# sustentationAvecPC.net
KiCad netlist of a schematic drawn in Altium Designer
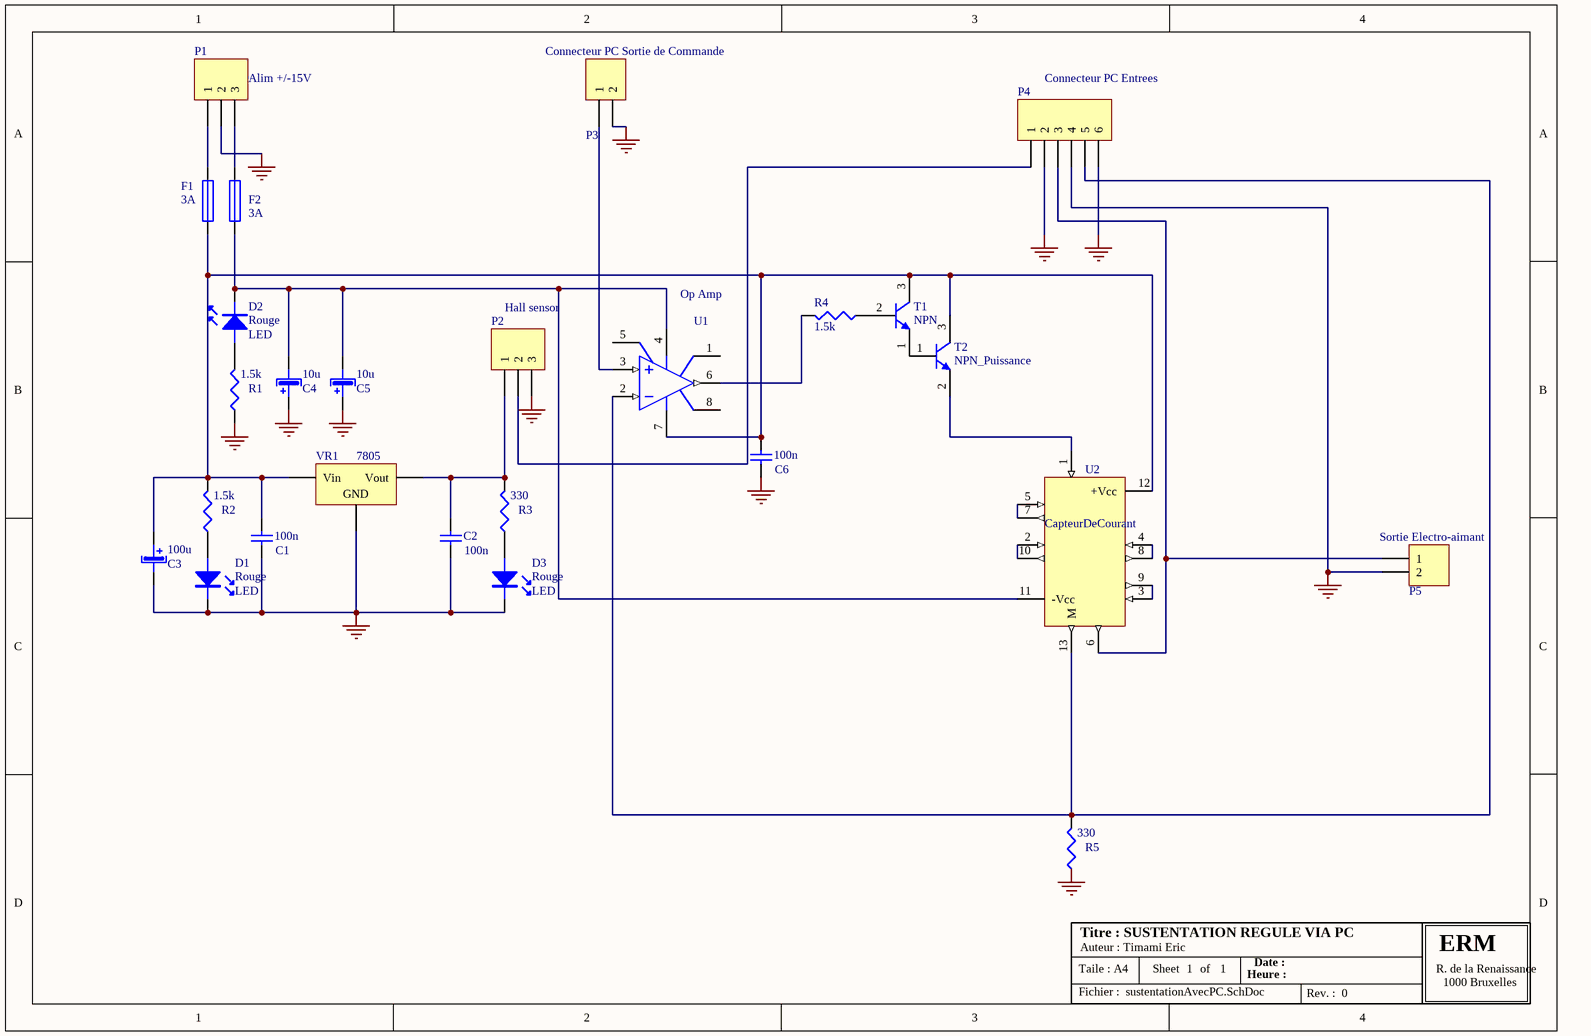
[diagram p0: sustentationAvecPC.SchDoc]

(export (version "E")
  (design (tool "Eeschema 10.0.6"))
  (components
    (comp (ref "C1")
      (value "100n")
      (footprint "Capa_100n")
      (description "Condensateur")
      (fields (field (name "DESIGNER") "ECAM 2004"))
      (libsource (lib "AntiNuisibles") (part "Condensateur"))
    )
    (comp (ref "C2")
      (value "100n")
      (footprint "Capa_100n")
      (description "Condensateur")
      (fields (field (name "DESIGNER") "ECAM 2004"))
      (libsource (lib "sustentationAvecPC") (part "Condensateur"))
    )
    (comp (ref "C3")
      (value "100u")
      (footprint "AXIAL-1.0")
      (description "Condensateur polatisé")
      (fields (field (name "Comment") "Cond pol radial") (field (name "DESIGNER") "ECAM 2004"))
      (libsource (lib "sustentationAvecPC") (part "Cond pol radial"))
    )
    (comp (ref "C4")
      (value "10u")
      (footprint "CAPPR_100u")
      (description "Condensateur polatisé")
      (fields (field (name "Comment") "Cond pol radial") (field (name "DESIGNER") "ECAM 2004"))
      (libsource (lib "sustentationAvecPC") (part "Cond pol radial"))
    )
    (comp (ref "C5")
      (value "10u")
      (footprint "CAPPR_100u")
      (description "Condensateur polatisé")
      (fields (field (name "Comment") "Cond pol  rad") (field (name "DESIGNER") "ECAM 2004"))
      (libsource (lib "sustentationAvecPC") (part "Cond pol radial"))
    )
    (comp (ref "C6")
      (value "100n")
      (footprint "Capa_100n")
      (description "Condensateur")
      (fields (field (name "DESIGNER") "ECAM 2004"))
      (libsource (lib "sustentationAvecPC") (part "Condensateur"))
    )
    (comp (ref "D1")
      (value "LED")
      (footprint "Led 0.1")
      (fields (field (name "COLOR") "Rouge") (field (name "DESIGNER") "ECAM 2004"))
      (libsource (lib "sustentationAvecPC") (part "LED"))
    )
    (comp (ref "D2")
      (value "LED")
      (footprint "Led 0.1")
      (fields (field (name "COLOR") "Rouge") (field (name "DESIGNER") "ECAM 2004"))
      (libsource (lib "sustentationAvecPC") (part "LED"))
    )
    (comp (ref "D3")
      (value "LED")
      (footprint "Led 0.1")
      (fields (field (name "COLOR") "Rouge") (field (name "DESIGNER") "ECAM 2004"))
      (libsource (lib "sustentationAvecPC") (part "LED"))
    )
    (comp (ref "F1")
      (value "3A")
      (footprint "FUSE-10")
      (description "Fusible")
      (fields (field (name "DESIGNER") "ECAM 2004"))
      (libsource (lib "*") (part "Fusible"))
    )
    (comp (ref "F2")
      (value "3A")
      (footprint "FUSE-10")
      (description "Fusible")
      (fields (field (name "DESIGNER") "ECAM 2004"))
      (libsource (lib "*") (part "Fusible"))
    )
    (comp (ref "P1")
      (value "Alim +/-15V")
      (footprint "CONVIS-3")
      (description "Header, 3-Pin")
      (fields (field (name "PUBLISHER") "Altium Limited"))
      (libsource (lib "sustentationAvecPC") (part "connecteur 3"))
    )
    (comp (ref "P2")
      (value "Hall sensor")
      (footprint "connecteur capteur Hall")
      (description "Header, 3-Pin")
      (fields (field (name "PUBLISHER") "Altium Limited"))
      (libsource (lib "sustentationAvecPC") (part "connecteur 3"))
    )
    (comp (ref "P3")
      (value "Connecteur PC Sortie de Commande")
      (footprint "connecteur PC Sorties command")
      (description "Connecteur")
      (fields (field (name "DESIGNER") "ECAM 2005"))
      (libsource (lib "") (part "Connecteur 2_1"))
    )
    (comp (ref "P4")
      (value "Connecteur PC Entrees")
      (footprint "connecteur PC Entrées")
      (description "Header, 6-Pin")
      (fields (field (name "PUBLISHER") "Altium Limited"))
      (libsource (lib "sustentationAvecPC") (part "Header 6"))
    )
    (comp (ref "P5")
      (value "Sortie Electro-aimant")
      (footprint "connecteur 3A")
      (description "Connecteur")
      (fields (field (name "DESIGNER") "ECAM 2005"))
      (libsource (lib "sustentationAvecPC") (part "Connecteur 2"))
    )
    (comp (ref "R1")
      (value "1.5k")
      (footprint "AXIAL-0.4")
      (description "Résistance standard")
      (fields (field (name "Comment") "Résistance") (field (name "DESIGNER") "ECAM 2005"))
      (libsource (lib "sustentationAvecPC") (part "Résistance"))
    )
    (comp (ref "R2")
      (value "1.5k")
      (footprint "AXIAL-0.4")
      (description "Résistance standard")
      (fields (field (name "Comment") "Résistance") (field (name "DESIGNER") "ECAM 2005"))
      (libsource (lib "sustentationAvecPC") (part "Résistance"))
    )
    (comp (ref "R3")
      (value "330")
      (footprint "AXIAL-0.4")
      (description "Résistance standard")
      (fields (field (name "Comment") "Résistance") (field (name "DESIGNER") "ECAM 2005"))
      (libsource (lib "sustentationAvecPC") (part "Résistance"))
    )
    (comp (ref "R4")
      (value "1.5k")
      (footprint "AXIAL-0.4")
      (description "Résistance standard")
      (fields (field (name "Comment") "Résistance") (field (name "DESIGNER") "ECAM 2005"))
      (libsource (lib "sustentationAvecPC") (part "Résistance"))
    )
    (comp (ref "R5")
      (value "330")
      (footprint "AXIAL-0.4")
      (description "Résistance standard")
      (fields (field (name "Comment") "Résistance") (field (name "DESIGNER") "ECAM 2005"))
      (libsource (lib "sustentationAvecPC") (part "Résistance"))
    )
    (comp (ref "T1")
      (value "NPN")
      (footprint "TO-5")
      (description "NPN Bipolar Transistor")
      (fields (field (name "PUBLISHER") "Altium Limited"))
      (libsource (lib "sustentationAvecPC") (part "NPN"))
    )
    (comp (ref "T2")
      (value "NPN_Puissance")
      (footprint "TO-3")
      (description "NPN Bipolar Transistor")
      (fields (field (name "PUBLISHER") "Altium Limited"))
      (libsource (lib "sustentationAvecPC") (part "NPN_Puissance"))
    )
    (comp (ref "U1")
      (value "Op Amp")
      (footprint "DIP8")
      (description "FET Operational Amplifier")
      (fields (field (name "PUBLISHER") "Altium Limited"))
      (libsource (lib "sustentationAvecPC") (part "Op Amp"))
    )
    (comp (ref "U2")
      (value "CapteurDeCourant")
      (footprint "Sonde_Courant")
      (fields (field (name "PUBLISHER") "Altium Limited"))
      (libsource (lib "sustentationAvecPC") (part "CapteurDeCourant"))
    )
    (comp (ref "VR1")
      (value "7805")
      (footprint "TO-220 regulateur")
      (description "Voltage Regulator")
      (fields (field (name "PUBLISHER") "Altium Limited"))
      (libsource (lib "sustentationAvecPC") (part "Volt Reg"))
    )
  )
  (nets
    (net (code "1") (name "GND") (class "Default")
      (node (ref "C1") (pin "2") (pinfunction "2_2") (pintype "passive"))
      (node (ref "C2") (pin "2") (pinfunction "2_2") (pintype "passive"))
      (node (ref "C3") (pin "2") (pinfunction "-_2") (pintype "passive"))
      (node (ref "C4") (pin "1") (pinfunction "+_1") (pintype "passive"))
      (node (ref "C5") (pin "1") (pinfunction "+_1") (pintype "passive"))
      (node (ref "C6") (pin "2") (pinfunction "2_2") (pintype "passive"))
      (node (ref "D1") (pin "2") (pinfunction "K_2") (pintype "passive"))
      (node (ref "D3") (pin "2") (pinfunction "K_2") (pintype "passive"))
      (node (ref "P1") (pin "2") (pinfunction "2_2") (pintype "passive"))
      (node (ref "P2") (pin "3") (pinfunction "3_3") (pintype "passive"))
      (node (ref "P3") (pin "2") (pinfunction "2_2") (pintype "passive"))
      (node (ref "P4") (pin "2") (pinfunction "2_2") (pintype "passive"))
      (node (ref "P4") (pin "4") (pinfunction "4_4") (pintype "passive"))
      (node (ref "P4") (pin "6") (pinfunction "6_6") (pintype "passive"))
      (node (ref "P5") (pin "2") (pinfunction "2_2") (pintype "passive"))
      (node (ref "R1") (pin "1") (pinfunction "1_1") (pintype "passive"))
      (node (ref "VR1") (pin "2") (pinfunction "GND_2") (pintype "passive"))
    )
    (net (code "2") (name "Net-(C3-+)") (class "Default")
      (node (ref "C1") (pin "1") (pinfunction "1_1") (pintype "passive"))
      (node (ref "C3") (pin "1") (pinfunction "+_1") (pintype "passive"))
      (node (ref "C6") (pin "1") (pinfunction "1_1") (pintype "passive"))
      (node (ref "F1") (pin "2") (pinfunction "F2_2") (pintype "passive"))
      (node (ref "R2") (pin "2") (pinfunction "2_2") (pintype "passive"))
      (node (ref "T1") (pin "3") (pinfunction "C_3") (pintype "passive"))
      (node (ref "T2") (pin "3") (pinfunction "C_3") (pintype "passive"))
      (node (ref "U1") (pin "7") (pinfunction "V+_7") (pintype "power_in"))
      (node (ref "U2") (pin "12") (pinfunction "+Vcc_12") (pintype "power_in"))
      (node (ref "VR1") (pin "1") (pinfunction "Vin_1") (pintype "passive"))
    )
    (net (code "3") (name "Net-(C4--)") (class "Default")
      (node (ref "C4") (pin "2") (pinfunction "-_2") (pintype "passive"))
      (node (ref "C5") (pin "2") (pinfunction "-_2") (pintype "passive"))
      (node (ref "D2") (pin "2") (pinfunction "K_2") (pintype "passive"))
      (node (ref "F2") (pin "2") (pinfunction "F2_2") (pintype "passive"))
      (node (ref "U1") (pin "4") (pinfunction "V-_4") (pintype "power_in"))
      (node (ref "U2") (pin "11") (pinfunction "-Vcc_11") (pintype "power_in"))
    )
    (net (code "4") (name "Net-(D1-A)") (class "Default")
      (node (ref "D1") (pin "1") (pinfunction "A_1") (pintype "passive"))
      (node (ref "R2") (pin "1") (pinfunction "1_1") (pintype "passive"))
    )
    (net (code "5") (name "Net-(D2-A)") (class "Default")
      (node (ref "D2") (pin "1") (pinfunction "A_1") (pintype "passive"))
      (node (ref "R1") (pin "2") (pinfunction "2_2") (pintype "passive"))
    )
    (net (code "6") (name "Net-(D3-A)") (class "Default")
      (node (ref "D3") (pin "1") (pinfunction "A_1") (pintype "passive"))
      (node (ref "R3") (pin "1") (pinfunction "1_1") (pintype "passive"))
    )
    (net (code "7") (name "Net-(F1-F1)") (class "Default")
      (node (ref "F1") (pin "1") (pinfunction "F1_1") (pintype "passive"))
      (node (ref "P1") (pin "1") (pinfunction "1_1") (pintype "passive"))
    )
    (net (code "8") (name "Net-(F2-F1)") (class "Default")
      (node (ref "F2") (pin "1") (pinfunction "F1_1") (pintype "passive"))
      (node (ref "P1") (pin "3") (pinfunction "3_3") (pintype "passive"))
    )
    (net (code "9") (name "Net-(P2-Pad2)") (class "Default")
      (node (ref "P2") (pin "2") (pinfunction "2_2") (pintype "passive"))
      (node (ref "P4") (pin "1") (pinfunction "1_1") (pintype "passive"))
    )
    (net (code "10") (name "Net-(P4-Pad3)") (class "Default")
      (node (ref "P4") (pin "3") (pinfunction "3_3") (pintype "passive"))
      (node (ref "P5") (pin "1") (pinfunction "1_1") (pintype "passive"))
      (node (ref "U2") (pin "6") (pintype "output"))
    )
    (net (code "11") (name "Net-(T1-B)") (class "Default")
      (node (ref "R4") (pin "1") (pinfunction "1_1") (pintype "passive"))
      (node (ref "T1") (pin "2") (pinfunction "B_2") (pintype "passive"))
    )
    (net (code "12") (name "Net-(T1-E)") (class "Default")
      (node (ref "T1") (pin "1") (pinfunction "E_1") (pintype "passive"))
      (node (ref "T2") (pin "1") (pinfunction "B_1") (pintype "passive"))
    )
    (net (code "13") (name "Net-(T2-E)") (class "Default")
      (node (ref "T2") (pin "2") (pinfunction "E_2") (pintype "passive"))
      (node (ref "U2") (pin "1") (pintype "input"))
    )
    (net (code "14") (name "Net-(U1-IN+)") (class "Default")
      (node (ref "P3") (pin "1") (pinfunction "1_1") (pintype "passive"))
      (node (ref "U1") (pin "3") (pinfunction "IN+_3") (pintype "input"))
    )
    (net (code "15") (name "Net-(U1-IN-)") (class "Default")
      (node (ref "P4") (pin "5") (pinfunction "5_5") (pintype "passive"))
      (node (ref "R5") (pin "2") (pinfunction "2_2") (pintype "passive"))
      (node (ref "U1") (pin "2") (pinfunction "IN-_2") (pintype "input"))
      (node (ref "U2") (pin "13") (pinfunction "M_13") (pintype "output"))
    )
    (net (code "16") (name "Net-(U1-OUT)") (class "Default")
      (node (ref "R4") (pin "2") (pinfunction "2_2") (pintype "passive"))
      (node (ref "U1") (pin "6") (pinfunction "OUT_6") (pintype "output"))
    )
    (net (code "17") (name "Net-(U2-Pad3)") (class "Default")
      (node (ref "U2") (pin "3") (pintype "input"))
      (node (ref "U2") (pin "9") (pintype "output"))
    )
    (net (code "18") (name "Net-(U2-Pad4)") (class "Default")
      (node (ref "U2") (pin "4") (pintype "input"))
      (node (ref "U2") (pin "8") (pintype "output"))
    )
    (net (code "19") (name "Net-(U2-Pad5)") (class "Default")
      (node (ref "U2") (pin "5") (pintype "input"))
      (node (ref "U2") (pin "7") (pintype "output"))
    )
    (net (code "20") (name "Net-(U2-Pad10)") (class "Default")
      (node (ref "U2") (pin "10") (pintype "output"))
      (node (ref "U2") (pin "2") (pintype "input"))
    )
    (net (code "21") (name "Net-(VR1-Vout)") (class "Default")
      (node (ref "C2") (pin "1") (pinfunction "1_1") (pintype "passive"))
      (node (ref "P2") (pin "1") (pinfunction "1_1") (pintype "passive"))
      (node (ref "R3") (pin "2") (pinfunction "2_2") (pintype "passive"))
      (node (ref "VR1") (pin "3") (pinfunction "Vout_3") (pintype "passive"))
    )
    (net (code "22") (name "unconnected-(R5-Pad1)") (class "Default")
      (node (ref "R5") (pin "1") (pinfunction "1_1") (pintype "passive"))
    )
    (net (code "23") (name "unconnected-(U1-OS_NUL-Pad1)") (class "Default")
      (node (ref "U1") (pin "1") (pinfunction "OS_NUL_1") (pintype "passive"))
    )
    (net (code "24") (name "unconnected-(U1-OS_NUL-Pad5)") (class "Default")
      (node (ref "U1") (pin "5") (pinfunction "OS_NUL_5") (pintype "passive"))
    )
    (net (code "25") (name "unconnected-(U1-TAB-Pad8)") (class "Default")
      (node (ref "U1") (pin "8") (pinfunction "TAB_8") (pintype "passive"))
    )
  )
)
